# ATTAMI-Shield-template.net
KiCad netlist of a schematic drawn in EAGLE
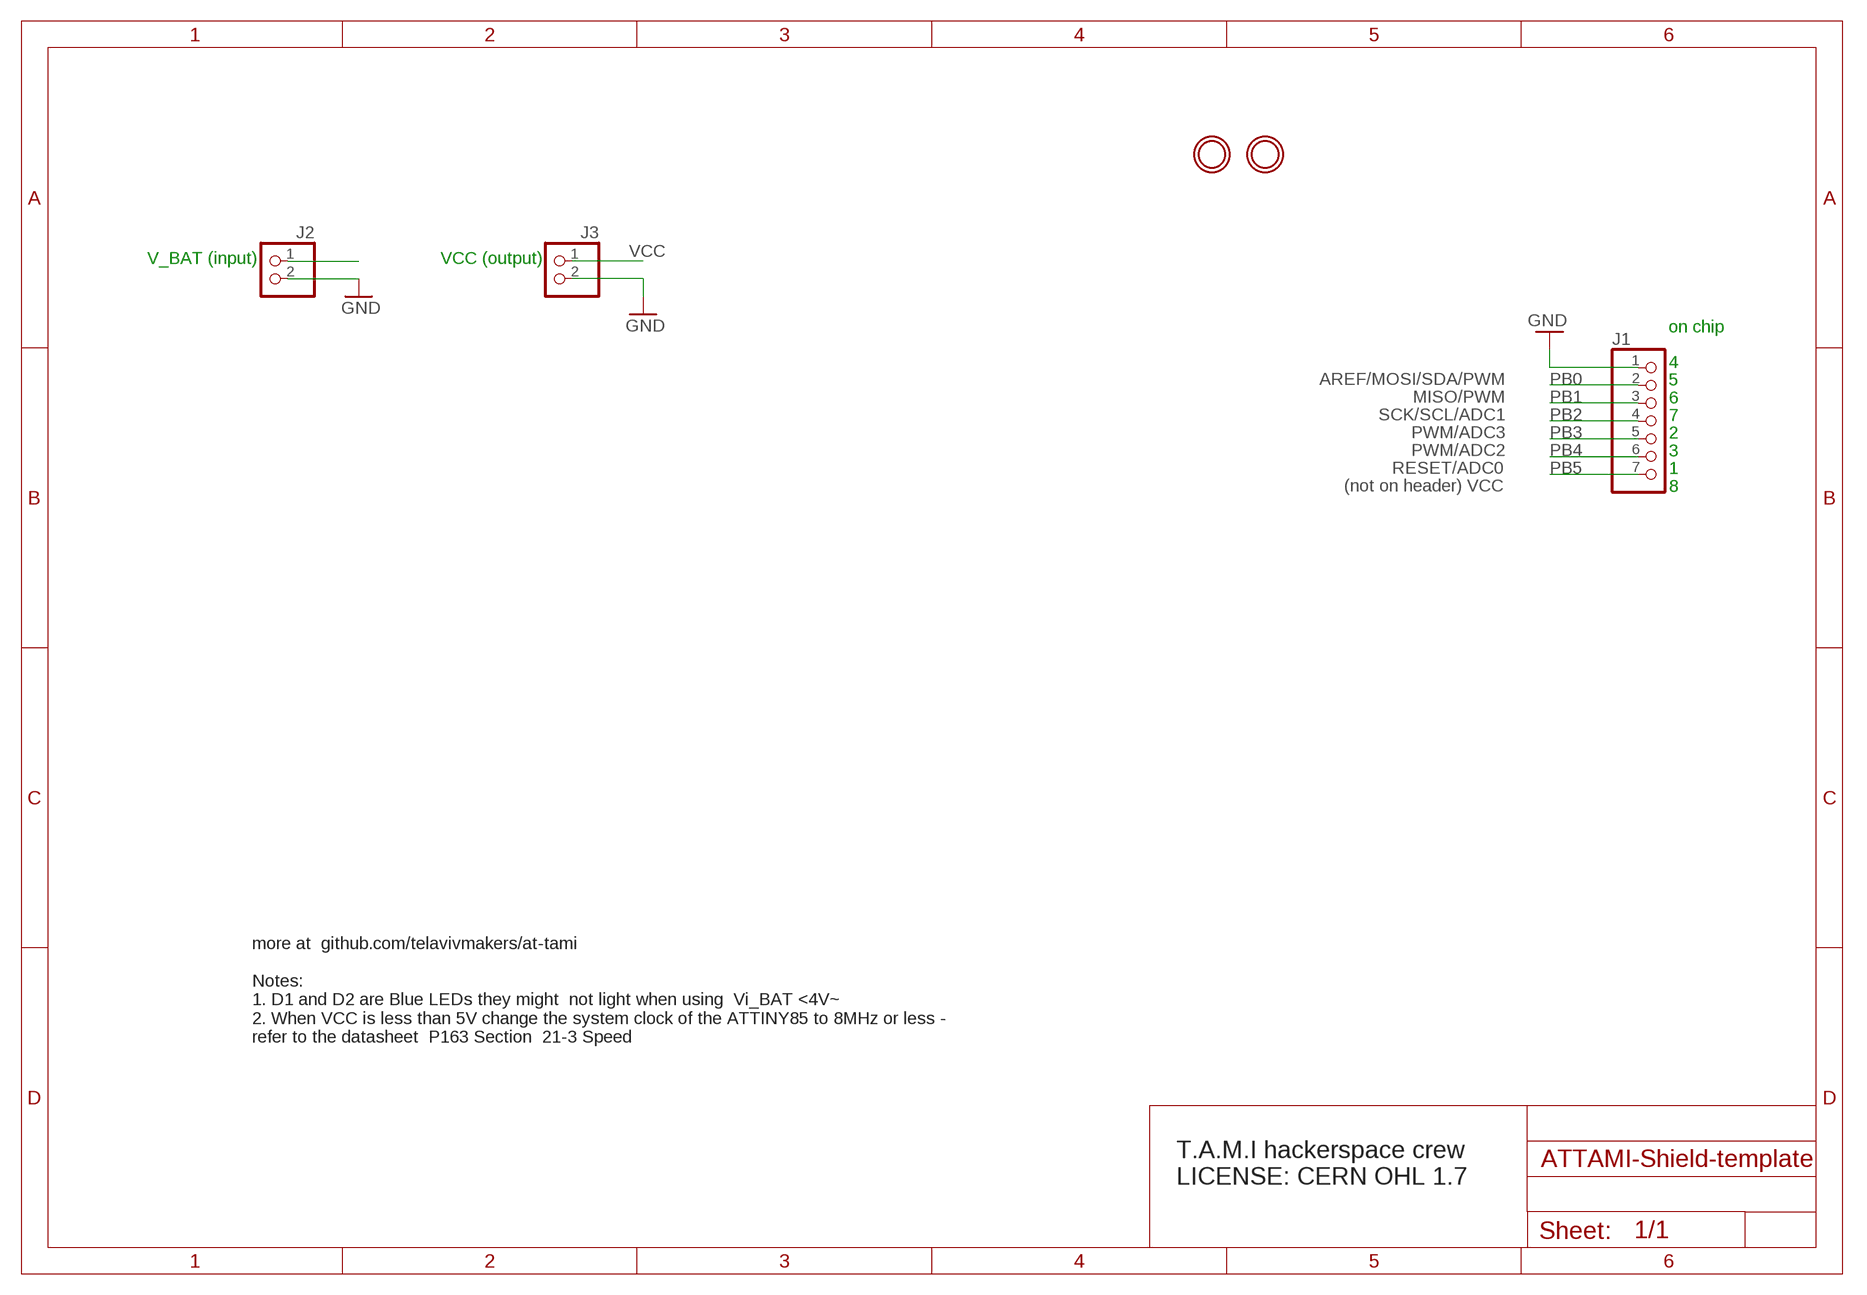
[diagram p0: schematic, sheet 1]

(export (version "E")
  (design (tool "Eeschema 10.0.6"))
  (components
    (comp (ref "J1")
      (value "HEADER-1X7ROUND")
      (footprint "eagle-import:1X07_ROUND")
      (libsource (lib "eagle-import") (part "HEADER-1X7ROUND"))
    )
    (comp (ref "J2")
      (value "HEADER-1X2ROUND")
      (footprint "eagle-import:1X02_ROUND")
      (libsource (lib "eagle-import") (part "HEADER-1X2ROUND"))
    )
    (comp (ref "J3")
      (value "HEADER-1X2ROUND")
      (footprint "eagle-import:1X02_ROUND")
      (libsource (lib "eagle-import") (part "HEADER-1X2ROUND"))
    )
    (comp (ref "U$1")
      (value "MOUNTINGHOLE2.0")
      (footprint "eagle-import:MOUNTINGHOLE_2.0_PLATED")
      (libsource (lib "eagle-import") (part "MOUNTINGHOLE2.0"))
    )
    (comp (ref "U$2")
      (value "MOUNTINGHOLE2.0")
      (footprint "eagle-import:MOUNTINGHOLE_2.0_PLATED")
      (libsource (lib "eagle-import") (part "MOUNTINGHOLE2.0"))
    )
  )
  (nets
    (net (code "1") (name "/PB0") (class "Default")
      (node (ref "J1") (pin "2") (pinfunction "2_2") (pintype "passive"))
    )
    (net (code "2") (name "/PB1") (class "Default")
      (node (ref "J1") (pin "3") (pinfunction "3_3") (pintype "passive"))
    )
    (net (code "3") (name "/PB2") (class "Default")
      (node (ref "J1") (pin "4") (pinfunction "4_4") (pintype "passive"))
    )
    (net (code "4") (name "/PB3") (class "Default")
      (node (ref "J1") (pin "5") (pinfunction "5_5") (pintype "passive"))
    )
    (net (code "5") (name "/PB4") (class "Default")
      (node (ref "J1") (pin "6") (pinfunction "6_6") (pintype "passive"))
    )
    (net (code "6") (name "/PB5") (class "Default")
      (node (ref "J1") (pin "7") (pinfunction "7_7") (pintype "passive"))
    )
    (net (code "7") (name "/VCC") (class "Default")
      (node (ref "J3") (pin "1") (pinfunction "1_1") (pintype "passive"))
    )
    (net (code "8") (name "GND") (class "Default")
      (node (ref "J1") (pin "1") (pinfunction "1_1") (pintype "passive"))
      (node (ref "J2") (pin "2") (pinfunction "2_2") (pintype "passive"))
      (node (ref "J3") (pin "2") (pinfunction "2_2") (pintype "passive"))
    )
    (net (code "9") (name "unconnected-(J2-Pad1)") (class "Default")
      (node (ref "J2") (pin "1") (pinfunction "1_1") (pintype "passive"))
    )
  )
)
